# FAT42.net
KiCad netlist of a schematic drawn in Altium Designer
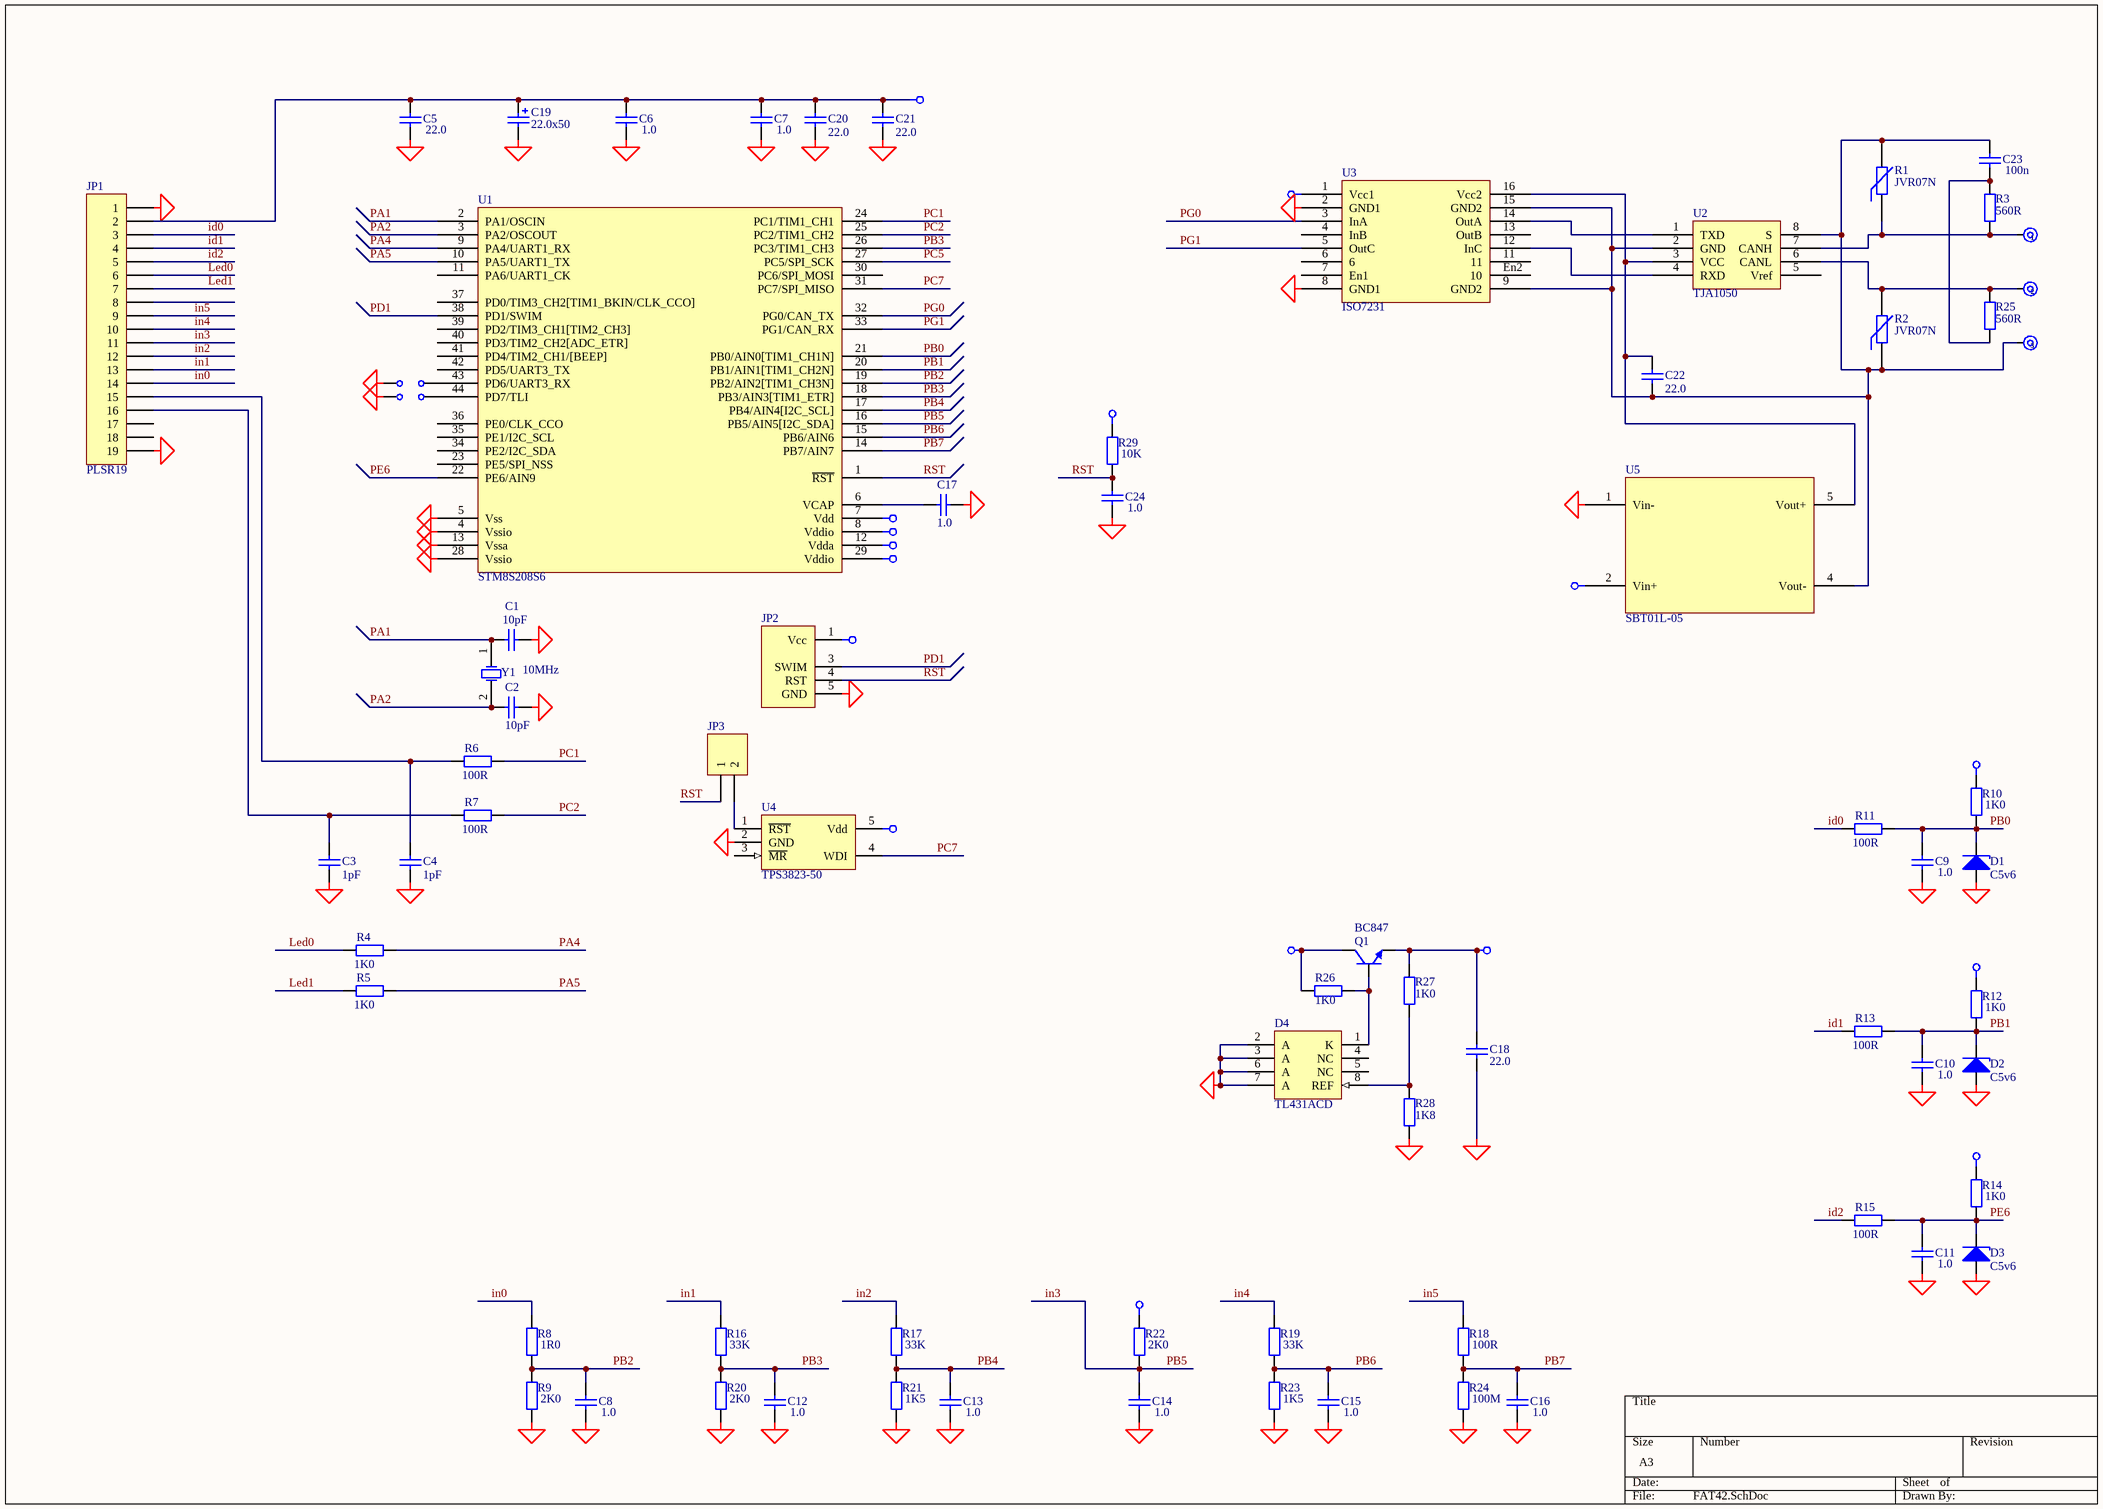
[diagram p0: FAT42.SchDoc]

(export (version "E")
  (design (tool "Eeschema 10.0.6"))
  (components
    (comp (ref "1")
      (value "~")
      (footprint "PIN2R")
      (description "Socket")
      (fields (field (name "MANUFACTURER") "Generic Components") (field (name "PUBLISHER") "Altium Limited"))
      (libsource (lib "PAL") (part "Socket_Ring"))
    )
    (comp (ref "2")
      (value "~")
      (footprint "PIN2R")
      (description "Socket")
      (fields (field (name "MANUFACTURER") "Generic Components") (field (name "PUBLISHER") "Altium Limited"))
      (libsource (lib "PAL") (part "Socket_Ring"))
    )
    (comp (ref "3")
      (value "~")
      (footprint "PIN2R")
      (description "Socket")
      (fields (field (name "MANUFACTURER") "Generic Components") (field (name "PUBLISHER") "Altium Limited"))
      (libsource (lib "PAL") (part "Socket_Ring"))
    )
    (comp (ref "C1")
      (value "10pF")
      (footprint "_1206")
      (description "Capacitor (Semiconductor SIM Model)")
      (fields (field (name "MANUFACTURER") "Generic Components") (field (name "PUBLISHER") "Altium Limited"))
      (libsource (lib "Miscellaneous Devices") (part "Cap Semi"))
    )
    (comp (ref "C2")
      (value "10pF")
      (footprint "_1206")
      (description "Capacitor (Semiconductor SIM Model)")
      (fields (field (name "MANUFACTURER") "Generic Components") (field (name "PUBLISHER") "Altium Limited"))
      (libsource (lib "Miscellaneous Devices") (part "Cap Semi"))
    )
    (comp (ref "C3")
      (value "1pF")
      (footprint "_1206")
      (description "Capacitor (Semiconductor SIM Model)")
      (fields (field (name "MANUFACTURER") "Generic Components") (field (name "PUBLISHER") "Altium Limited"))
      (libsource (lib "Miscellaneous Devices") (part "Cap Semi"))
    )
    (comp (ref "C4")
      (value "1pF")
      (footprint "_1206")
      (description "Capacitor (Semiconductor SIM Model)")
      (fields (field (name "MANUFACTURER") "Generic Components") (field (name "PUBLISHER") "Altium Limited"))
      (libsource (lib "Miscellaneous Devices") (part "Cap Semi"))
    )
    (comp (ref "C5")
      (value "22.0")
      (footprint "_1206")
      (description "Capacitor (Semiconductor SIM Model)")
      (fields (field (name "MANUFACTURER") "Generic Components") (field (name "PUBLISHER") "Altium Limited"))
      (libsource (lib "Miscellaneous Devices") (part "Cap Semi"))
    )
    (comp (ref "C6")
      (value "1.0")
      (footprint "_1206")
      (description "Capacitor (Semiconductor SIM Model)")
      (fields (field (name "MANUFACTURER") "Generic Components") (field (name "PUBLISHER") "Altium Limited"))
      (libsource (lib "Miscellaneous Devices") (part "Cap Semi"))
    )
    (comp (ref "C7")
      (value "1.0")
      (footprint "_1206")
      (description "Capacitor (Semiconductor SIM Model)")
      (fields (field (name "MANUFACTURER") "Generic Components") (field (name "PUBLISHER") "Altium Limited"))
      (libsource (lib "Miscellaneous Devices") (part "Cap Semi"))
    )
    (comp (ref "C8")
      (value "1.0")
      (footprint "_1206")
      (description "Capacitor (Semiconductor SIM Model)")
      (fields (field (name "MANUFACTURER") "Generic Components") (field (name "PUBLISHER") "Altium Limited"))
      (libsource (lib "Miscellaneous Devices") (part "Cap Semi"))
    )
    (comp (ref "C9")
      (value "1.0")
      (footprint "_1206")
      (description "Capacitor (Semiconductor SIM Model)")
      (fields (field (name "MANUFACTURER") "Generic Components") (field (name "PUBLISHER") "Altium Limited"))
      (libsource (lib "Miscellaneous Devices") (part "Cap Semi"))
    )
    (comp (ref "C10")
      (value "1.0")
      (footprint "_1206")
      (description "Capacitor (Semiconductor SIM Model)")
      (fields (field (name "MANUFACTURER") "Generic Components") (field (name "PUBLISHER") "Altium Limited"))
      (libsource (lib "Miscellaneous Devices") (part "Cap Semi"))
    )
    (comp (ref "C11")
      (value "1.0")
      (footprint "_1206")
      (description "Capacitor (Semiconductor SIM Model)")
      (fields (field (name "MANUFACTURER") "Generic Components") (field (name "PUBLISHER") "Altium Limited"))
      (libsource (lib "Miscellaneous Devices") (part "Cap Semi"))
    )
    (comp (ref "C12")
      (value "1.0")
      (footprint "_1206")
      (description "Capacitor (Semiconductor SIM Model)")
      (fields (field (name "MANUFACTURER") "Generic Components") (field (name "PUBLISHER") "Altium Limited"))
      (libsource (lib "Miscellaneous Devices") (part "Cap Semi"))
    )
    (comp (ref "C13")
      (value "1.0")
      (footprint "_1206")
      (description "Capacitor (Semiconductor SIM Model)")
      (fields (field (name "MANUFACTURER") "Generic Components") (field (name "PUBLISHER") "Altium Limited"))
      (libsource (lib "Miscellaneous Devices") (part "Cap Semi"))
    )
    (comp (ref "C14")
      (value "1.0")
      (footprint "_1206")
      (description "Capacitor (Semiconductor SIM Model)")
      (fields (field (name "MANUFACTURER") "Generic Components") (field (name "PUBLISHER") "Altium Limited"))
      (libsource (lib "Miscellaneous Devices") (part "Cap Semi"))
    )
    (comp (ref "C15")
      (value "1.0")
      (footprint "_1206")
      (description "Capacitor (Semiconductor SIM Model)")
      (fields (field (name "MANUFACTURER") "Generic Components") (field (name "PUBLISHER") "Altium Limited"))
      (libsource (lib "Miscellaneous Devices") (part "Cap Semi"))
    )
    (comp (ref "C16")
      (value "1.0")
      (footprint "_1206")
      (description "Capacitor (Semiconductor SIM Model)")
      (fields (field (name "MANUFACTURER") "Generic Components") (field (name "PUBLISHER") "Altium Limited"))
      (libsource (lib "Miscellaneous Devices") (part "Cap Semi"))
    )
    (comp (ref "C17")
      (value "1.0")
      (footprint "_1206")
      (description "Capacitor (Semiconductor SIM Model)")
      (fields (field (name "MANUFACTURER") "Generic Components") (field (name "PUBLISHER") "Altium Limited"))
      (libsource (lib "Miscellaneous Devices") (part "Cap Semi"))
    )
    (comp (ref "C18")
      (value "22.0")
      (footprint "_1206")
      (description "Capacitor (Semiconductor SIM Model)")
      (fields (field (name "MANUFACTURER") "Generic Components") (field (name "PUBLISHER") "Altium Limited"))
      (libsource (lib "Miscellaneous Devices") (part "Cap Semi"))
    )
    (comp (ref "C19")
      (value "22.0x50")
      (footprint "el3")
      (description "Polarized Capacitor (Radial)")
      (fields (field (name "MANUFACTURER") "Generic Components") (field (name "PUBLISHER") "Altium Limited"))
      (libsource (lib "PAL") (part "Cap Pol1"))
    )
    (comp (ref "C20")
      (value "22.0")
      (footprint "_1206")
      (description "Capacitor (Semiconductor SIM Model)")
      (fields (field (name "MANUFACTURER") "Generic Components") (field (name "PUBLISHER") "Altium Limited"))
      (libsource (lib "Miscellaneous Devices") (part "Cap Semi"))
    )
    (comp (ref "C21")
      (value "22.0")
      (footprint "_1206")
      (description "Capacitor (Semiconductor SIM Model)")
      (fields (field (name "MANUFACTURER") "Generic Components") (field (name "PUBLISHER") "Altium Limited"))
      (libsource (lib "Miscellaneous Devices") (part "Cap Semi"))
    )
    (comp (ref "C22")
      (value "22.0")
      (footprint "_1206")
      (description "Capacitor (Semiconductor SIM Model)")
      (fields (field (name "MANUFACTURER") "Generic Components") (field (name "PUBLISHER") "Altium Limited"))
      (libsource (lib "Miscellaneous Devices") (part "Cap Semi"))
    )
    (comp (ref "C23")
      (value "100n")
      (footprint "_1206")
      (description "Capacitor (Semiconductor SIM Model)")
      (fields (field (name "MANUFACTURER") "Generic Components") (field (name "PUBLISHER") "Altium Limited"))
      (libsource (lib "Miscellaneous Devices") (part "Cap Semi"))
    )
    (comp (ref "C24")
      (value "1.0")
      (footprint "_1206")
      (description "Capacitor (Semiconductor SIM Model)")
      (fields (field (name "MANUFACTURER") "Generic Components") (field (name "PUBLISHER") "Altium Limited"))
      (libsource (lib "Miscellaneous Devices") (part "Cap Semi"))
    )
    (comp (ref "D1")
      (value "C5v6")
      (footprint "_1206d")
      (description "Default Diode")
      (fields (field (name "MANUFACTURER") "Generic Components") (field (name "PUBLISHER") "Altium Limited"))
      (libsource (lib "PAL") (part "Zener"))
    )
    (comp (ref "D2")
      (value "C5v6")
      (footprint "_1206d")
      (description "Default Diode")
      (fields (field (name "MANUFACTURER") "Generic Components") (field (name "PUBLISHER") "Altium Limited"))
      (libsource (lib "PAL") (part "Zener"))
    )
    (comp (ref "D3")
      (value "C5v6")
      (footprint "_1206d")
      (description "Default Diode")
      (fields (field (name "MANUFACTURER") "Generic Components") (field (name "PUBLISHER") "Altium Limited"))
      (libsource (lib "PAL") (part "Zener"))
    )
    (comp (ref "D4")
      (value "TL431ACD")
      (footprint "SO-G8")
      (description "Programmable Precision Reference")
      (fields (field (name "MANUFACTURER") "Motorola") (field (name "PUBLISHER") "Altium Limited"))
      (libsource (lib "Motorola Power Management Voltage Reference") (part "TL431ACD"))
    )
    (comp (ref "J1")
      (value "~")
      (footprint "jmp")
      (description "Switch")
      (fields (field (name "MANUFACTURER") "Generic Components") (field (name "PUBLISHER") "Altium Limited"))
      (libsource (lib "PAL") (part "JMP"))
    )
    (comp (ref "J2")
      (value "~")
      (footprint "jmp")
      (description "Switch")
      (fields (field (name "MANUFACTURER") "Generic Components") (field (name "PUBLISHER") "Altium Limited"))
      (libsource (lib "PAL") (part "JMP"))
    )
    (comp (ref "JP1")
      (value "PLSR19")
      (footprint "HDR1X19")
      (description "Header, 19-Pin")
      (fields (field (name "MANUFACTURER") "Generic Components") (field (name "PUBLISHER") "Altium Limited"))
      (libsource (lib "Miscellaneous Connectors") (part "Header 19"))
    )
    (comp (ref "JP2") (value "~") (footprint "HDR1X5_uart") (libsource (lib "PAL") (part "SWIM_CONN")))
    (comp (ref "JP3")
      (value "PLS2")
      (footprint "HDR1X2")
      (description "Header, 2-Pin")
      (fields (field (name "MANUFACTURER") "Generic Components") (field (name "PUBLISHER") "Altium Limited"))
      (libsource (lib "Miscellaneous Connectors") (part "Header 2"))
    )
    (comp (ref "Q1")
      (value "BC847")
      (footprint "SO-G3")
      (description "General Purpose Transistor NPN Silicon")
      (fields (field (name "MANUFACTURER") "Motorola") (field (name "PUBLISHER") "Altium Limited"))
      (libsource (lib "PAL") (part "BC847ALT1"))
    )
    (comp (ref "R1")
      (value "JVR07N")
      (footprint "JVR07N")
      (description "Varistor (Voltage-Sensitive Resistor)")
      (fields (field (name "MANUFACTURER") "Generic Components") (field (name "PUBLISHER") "Altium Limited"))
      (libsource (lib "Miscellaneous Devices") (part "Res Varistor"))
    )
    (comp (ref "R2")
      (value "JVR07N")
      (footprint "JVR07N")
      (description "Varistor (Voltage-Sensitive Resistor)")
      (fields (field (name "MANUFACTURER") "Generic Components") (field (name "PUBLISHER") "Altium Limited"))
      (libsource (lib "Miscellaneous Devices") (part "Res Varistor"))
    )
    (comp (ref "R3")
      (value "560R")
      (footprint "_1206")
      (description "Resistor")
      (fields (field (name "MANUFACTURER") "Generic Components") (field (name "PUBLISHER") "Altium Limited"))
      (libsource (lib "") (part "Res2_1"))
    )
    (comp (ref "R4")
      (value "1K0")
      (footprint "_1206")
      (description "Resistor")
      (fields (field (name "MANUFACTURER") "Generic Components") (field (name "PUBLISHER") "Altium Limited"))
      (libsource (lib "") (part "Res2_1"))
    )
    (comp (ref "R5")
      (value "1K0")
      (footprint "_1206")
      (description "Resistor")
      (fields (field (name "MANUFACTURER") "Generic Components") (field (name "PUBLISHER") "Altium Limited"))
      (libsource (lib "") (part "Res2_1"))
    )
    (comp (ref "R6")
      (value "100R")
      (footprint "_1206")
      (description "Resistor")
      (fields (field (name "MANUFACTURER") "Generic Components") (field (name "PUBLISHER") "Altium Limited"))
      (libsource (lib "") (part "Res2_2"))
    )
    (comp (ref "R7")
      (value "100R")
      (footprint "_1206")
      (description "Resistor")
      (fields (field (name "MANUFACTURER") "Generic Components") (field (name "PUBLISHER") "Altium Limited"))
      (libsource (lib "") (part "Res2_2"))
    )
    (comp (ref "R8")
      (value "1R0")
      (footprint "_1206")
      (description "Resistor")
      (fields (field (name "MANUFACTURER") "Generic Components") (field (name "PUBLISHER") "Altium Limited"))
      (libsource (lib "Miscellaneous Devices") (part "Res2"))
    )
    (comp (ref "R9")
      (value "2K0")
      (footprint "_1206")
      (description "Resistor")
      (fields (field (name "MANUFACTURER") "Generic Components") (field (name "PUBLISHER") "Altium Limited"))
      (libsource (lib "Miscellaneous Devices") (part "Res2"))
    )
    (comp (ref "R10")
      (value "1K0")
      (footprint "_1206")
      (description "Resistor")
      (fields (field (name "MANUFACTURER") "Generic Components") (field (name "PUBLISHER") "Altium Limited"))
      (libsource (lib "") (part "Res2_4"))
    )
    (comp (ref "R11")
      (value "100R")
      (footprint "_1206")
      (description "Resistor")
      (fields (field (name "MANUFACTURER") "Generic Components") (field (name "PUBLISHER") "Altium Limited"))
      (libsource (lib "") (part "Res2_2"))
    )
    (comp (ref "R12")
      (value "1K0")
      (footprint "_1206")
      (description "Resistor")
      (fields (field (name "MANUFACTURER") "Generic Components") (field (name "PUBLISHER") "Altium Limited"))
      (libsource (lib "") (part "Res2_4"))
    )
    (comp (ref "R13")
      (value "100R")
      (footprint "_1206")
      (description "Resistor")
      (fields (field (name "MANUFACTURER") "Generic Components") (field (name "PUBLISHER") "Altium Limited"))
      (libsource (lib "") (part "Res2_2"))
    )
    (comp (ref "R14")
      (value "1K0")
      (footprint "_1206")
      (description "Resistor")
      (fields (field (name "MANUFACTURER") "Generic Components") (field (name "PUBLISHER") "Altium Limited"))
      (libsource (lib "") (part "Res2_4"))
    )
    (comp (ref "R15")
      (value "100R")
      (footprint "_1206")
      (description "Resistor")
      (fields (field (name "MANUFACTURER") "Generic Components") (field (name "PUBLISHER") "Altium Limited"))
      (libsource (lib "") (part "Res2_2"))
    )
    (comp (ref "R16")
      (value "33K")
      (footprint "_1206")
      (description "Resistor")
      (fields (field (name "MANUFACTURER") "Generic Components") (field (name "PUBLISHER") "Altium Limited"))
      (libsource (lib "Miscellaneous Devices") (part "Res2"))
    )
    (comp (ref "R17")
      (value "33K")
      (footprint "_1206")
      (description "Resistor")
      (fields (field (name "MANUFACTURER") "Generic Components") (field (name "PUBLISHER") "Altium Limited"))
      (libsource (lib "Miscellaneous Devices") (part "Res2"))
    )
    (comp (ref "R18")
      (value "100R")
      (footprint "_1206")
      (description "Resistor")
      (fields (field (name "MANUFACTURER") "Generic Components") (field (name "PUBLISHER") "Altium Limited"))
      (libsource (lib "Miscellaneous Devices") (part "Res2"))
    )
    (comp (ref "R19")
      (value "33K")
      (footprint "_1206")
      (description "Resistor")
      (fields (field (name "MANUFACTURER") "Generic Components") (field (name "PUBLISHER") "Altium Limited"))
      (libsource (lib "Miscellaneous Devices") (part "Res2"))
    )
    (comp (ref "R20")
      (value "2K0")
      (footprint "_1206")
      (description "Resistor")
      (fields (field (name "MANUFACTURER") "Generic Components") (field (name "PUBLISHER") "Altium Limited"))
      (libsource (lib "Miscellaneous Devices") (part "Res2"))
    )
    (comp (ref "R21")
      (value "1K5")
      (footprint "_1206")
      (description "Resistor")
      (fields (field (name "MANUFACTURER") "Generic Components") (field (name "PUBLISHER") "Altium Limited"))
      (libsource (lib "Miscellaneous Devices") (part "Res2"))
    )
    (comp (ref "R22")
      (value "2K0")
      (footprint "_1206")
      (description "Resistor")
      (fields (field (name "MANUFACTURER") "Generic Components") (field (name "PUBLISHER") "Altium Limited"))
      (libsource (lib "Miscellaneous Devices") (part "Res2"))
    )
    (comp (ref "R23")
      (value "1K5")
      (footprint "_1206")
      (description "Resistor")
      (fields (field (name "MANUFACTURER") "Generic Components") (field (name "PUBLISHER") "Altium Limited"))
      (libsource (lib "Miscellaneous Devices") (part "Res2"))
    )
    (comp (ref "R24")
      (value "100M")
      (footprint "_1206")
      (description "Resistor")
      (fields (field (name "MANUFACTURER") "Generic Components") (field (name "PUBLISHER") "Altium Limited"))
      (libsource (lib "Miscellaneous Devices") (part "Res2"))
    )
    (comp (ref "R25")
      (value "560R")
      (footprint "_1206")
      (description "Resistor")
      (fields (field (name "MANUFACTURER") "Generic Components") (field (name "PUBLISHER") "Altium Limited"))
      (libsource (lib "") (part "Res2_1"))
    )
    (comp (ref "R26")
      (value "1K0")
      (footprint "_1206")
      (description "Resistor")
      (fields (field (name "MANUFACTURER") "Generic Components") (field (name "PUBLISHER") "Altium Limited"))
      (libsource (lib "") (part "Res2_3"))
    )
    (comp (ref "R27")
      (value "1K0")
      (footprint "_1206")
      (description "Resistor")
      (fields (field (name "MANUFACTURER") "Generic Components") (field (name "PUBLISHER") "Altium Limited"))
      (libsource (lib "") (part "Res2_1"))
    )
    (comp (ref "R28")
      (value "1K8")
      (footprint "_1206")
      (description "Resistor")
      (fields (field (name "MANUFACTURER") "Generic Components") (field (name "PUBLISHER") "Altium Limited"))
      (libsource (lib "") (part "Res2_1"))
    )
    (comp (ref "R29")
      (value "10K")
      (footprint "_1206")
      (description "Resistor")
      (fields (field (name "MANUFACTURER") "Generic Components") (field (name "PUBLISHER") "Altium Limited"))
      (libsource (lib "") (part "Res2_4"))
    )
    (comp (ref "U1")
      (value "STM8S208S6")
      (footprint "QFP10X10-G44/G10N")
      (libsource (lib "PAL") (part "STM8S208S6"))
    )
    (comp (ref "U2") (value "TJA1050") (footprint "SO-G8/D5") (libsource (lib "PAL") (part "TJA1050")))
    (comp (ref "U3") (value "ISO7231") (footprint "SO-G16/D10.4") (libsource (lib "PAL") (part "ISO7231")))
    (comp (ref "U4")
      (value "TPS3823-50")
      (footprint "SO-G5/P.95")
      (description "Reset IC")
      (fields
        (field (name "MANUFACTURER") "National Semiconductor")
        (field (name "PUBLISHER") "Altium Limited")
      )
      (libsource (lib "PAL") (part "TPS3823"))
    )
    (comp (ref "U5") (value "SBT01L-05") (footprint "SBT01DET01") (libsource (lib "PAL") (part "SBT01L")))
    (comp (ref "Y1")
      (value "10MHz")
      (footprint "QWARZ1")
      (description "Crystal Oscillator")
      (fields (field (name "MANUFACTURER") "Generic Components") (field (name "PUBLISHER") "Altium Limited"))
      (libsource (lib "Miscellaneous Devices") (part "XTAL"))
    )
  )
  (nets
    (net (code "1") (name "+5v") (class "Default")
      (node (ref "C19") (pin "1") (pinfunction "1_1") (pintype "passive"))
      (node (ref "C20") (pin "1") (pinfunction "1_1") (pintype "passive"))
      (node (ref "C21") (pin "1") (pinfunction "1_1") (pintype "passive"))
      (node (ref "C5") (pin "2") (pinfunction "2_2") (pintype "passive"))
      (node (ref "C6") (pin "2") (pinfunction "2_2") (pintype "passive"))
      (node (ref "C7") (pin "2") (pinfunction "2_2") (pintype "passive"))
      (node (ref "JP1") (pin "2") (pinfunction "2_2") (pintype "passive"))
      (node (ref "JP2") (pin "1") (pinfunction "Vcc_1") (pintype "passive"))
      (node (ref "Q1") (pin "3") (pinfunction "C_3") (pintype "passive"))
      (node (ref "R10") (pin "1") (pinfunction "1_1") (pintype "passive"))
      (node (ref "R12") (pin "1") (pinfunction "1_1") (pintype "passive"))
      (node (ref "R14") (pin "1") (pinfunction "1_1") (pintype "passive"))
      (node (ref "R22") (pin "2") (pinfunction "2_2") (pintype "passive"))
      (node (ref "R26") (pin "1") (pinfunction "1_1") (pintype "passive"))
      (node (ref "R29") (pin "1") (pinfunction "1_1") (pintype "passive"))
      (node (ref "U1") (pin "29") (pinfunction "Vddio_29") (pintype "passive"))
      (node (ref "U1") (pin "7") (pinfunction "Vdd_7") (pintype "passive"))
      (node (ref "U1") (pin "8") (pinfunction "Vddio_8") (pintype "passive"))
      (node (ref "U3") (pin "1") (pinfunction "Vcc1_1") (pintype "passive"))
      (node (ref "U4") (pin "5") (pinfunction "Vdd_5") (pintype "power_in"))
      (node (ref "U5") (pin "2") (pinfunction "Vin+_2") (pintype "passive"))
    )
    (net (code "2") (name "/Led0") (class "Default")
      (node (ref "JP1") (pin "6") (pinfunction "6_6") (pintype "passive"))
      (node (ref "R4") (pin "1") (pinfunction "1_1") (pintype "passive"))
    )
    (net (code "3") (name "/Led1") (class "Default")
      (node (ref "JP1") (pin "7") (pinfunction "7_7") (pintype "passive"))
      (node (ref "R5") (pin "1") (pinfunction "1_1") (pintype "passive"))
    )
    (net (code "4") (name "/PA1") (class "Default")
      (node (ref "C1") (pin "2") (pinfunction "2_2") (pintype "passive"))
      (node (ref "U1") (pin "2") (pinfunction "PA1/OSCIN_2") (pintype "passive"))
      (node (ref "Y1") (pin "1") (pinfunction "OSC1_1") (pintype "passive"))
    )
    (net (code "5") (name "/PA2") (class "Default")
      (node (ref "C2") (pin "2") (pinfunction "2_2") (pintype "passive"))
      (node (ref "U1") (pin "3") (pinfunction "PA2/OSCOUT_3") (pintype "passive"))
      (node (ref "Y1") (pin "2") (pinfunction "OSC2_2") (pintype "passive"))
    )
    (net (code "6") (name "/PA4") (class "Default")
      (node (ref "R4") (pin "2") (pinfunction "2_2") (pintype "passive"))
      (node (ref "U1") (pin "9") (pinfunction "PA4/UART1_RX_9") (pintype "passive"))
    )
    (net (code "7") (name "/PA5") (class "Default")
      (node (ref "R5") (pin "2") (pinfunction "2_2") (pintype "passive"))
      (node (ref "U1") (pin "10") (pinfunction "PA5/UART1_TX_10") (pintype "passive"))
    )
    (net (code "8") (name "/PB0") (class "Default")
      (node (ref "C9") (pin "2") (pinfunction "2_2") (pintype "passive"))
      (node (ref "D1") (pin "2") (pinfunction "K_2") (pintype "passive"))
      (node (ref "R10") (pin "2") (pinfunction "2_2") (pintype "passive"))
      (node (ref "R11") (pin "1") (pinfunction "1_1") (pintype "passive"))
      (node (ref "U1") (pin "21") (pinfunction "PB0/AIN0[TIM1_CH1N]_21") (pintype "passive"))
    )
    (net (code "9") (name "/PB1") (class "Default")
      (node (ref "C10") (pin "2") (pinfunction "2_2") (pintype "passive"))
      (node (ref "D2") (pin "2") (pinfunction "K_2") (pintype "passive"))
      (node (ref "R12") (pin "2") (pinfunction "2_2") (pintype "passive"))
      (node (ref "R13") (pin "1") (pinfunction "1_1") (pintype "passive"))
      (node (ref "U1") (pin "20") (pinfunction "PB1/AIN1[TIM1_CH2N]_20") (pintype "passive"))
    )
    (net (code "10") (name "/PB2") (class "Default")
      (node (ref "C8") (pin "2") (pinfunction "2_2") (pintype "passive"))
      (node (ref "R8") (pin "1") (pinfunction "1_1") (pintype "passive"))
      (node (ref "R9") (pin "2") (pinfunction "2_2") (pintype "passive"))
      (node (ref "U1") (pin "19") (pinfunction "PB2/AIN2[TIM1_CH3N]_19") (pintype "passive"))
    )
    (net (code "11") (name "/PB3") (class "Default")
      (node (ref "C12") (pin "2") (pinfunction "2_2") (pintype "passive"))
      (node (ref "R16") (pin "1") (pinfunction "1_1") (pintype "passive"))
      (node (ref "R20") (pin "2") (pinfunction "2_2") (pintype "passive"))
      (node (ref "U1") (pin "18") (pinfunction "PB3/AIN3[TIM1_ETR]_18") (pintype "passive"))
      (node (ref "U1") (pin "26") (pinfunction "PC3/TIM1_CH3_26") (pintype "passive"))
    )
    (net (code "12") (name "/PB4") (class "Default")
      (node (ref "C13") (pin "2") (pinfunction "2_2") (pintype "passive"))
      (node (ref "R17") (pin "1") (pinfunction "1_1") (pintype "passive"))
      (node (ref "R21") (pin "2") (pinfunction "2_2") (pintype "passive"))
      (node (ref "U1") (pin "17") (pinfunction "PB4/AIN4[I2C_SCL]_17") (pintype "passive"))
    )
    (net (code "13") (name "/PB5") (class "Default")
      (node (ref "C14") (pin "2") (pinfunction "2_2") (pintype "passive"))
      (node (ref "JP1") (pin "11") (pinfunction "11_11") (pintype "passive"))
      (node (ref "R22") (pin "1") (pinfunction "1_1") (pintype "passive"))
      (node (ref "U1") (pin "16") (pinfunction "PB5/AIN5[I2C_SDA]_16") (pintype "passive"))
    )
    (net (code "14") (name "/PB6") (class "Default")
      (node (ref "C15") (pin "2") (pinfunction "2_2") (pintype "passive"))
      (node (ref "R19") (pin "1") (pinfunction "1_1") (pintype "passive"))
      (node (ref "R23") (pin "2") (pinfunction "2_2") (pintype "passive"))
      (node (ref "U1") (pin "15") (pinfunction "PB6/AIN6_15") (pintype "passive"))
    )
    (net (code "15") (name "/PB7") (class "Default")
      (node (ref "C16") (pin "2") (pinfunction "2_2") (pintype "passive"))
      (node (ref "R18") (pin "1") (pinfunction "1_1") (pintype "passive"))
      (node (ref "R24") (pin "2") (pinfunction "2_2") (pintype "passive"))
      (node (ref "U1") (pin "14") (pinfunction "PB7/AIN7_14") (pintype "passive"))
    )
    (net (code "16") (name "/PC1") (class "Default")
      (node (ref "R6") (pin "1") (pinfunction "1_1") (pintype "passive"))
      (node (ref "U1") (pin "24") (pinfunction "PC1/TIM1_CH1_24") (pintype "passive"))
    )
    (net (code "17") (name "/PC2") (class "Default")
      (node (ref "R7") (pin "1") (pinfunction "1_1") (pintype "passive"))
      (node (ref "U1") (pin "25") (pinfunction "PC2/TIM1_CH2_25") (pintype "passive"))
    )
    (net (code "18") (name "/PC5") (class "Default")
      (node (ref "U1") (pin "27") (pinfunction "PC5/SPI_SCK_27") (pintype "passive"))
    )
    (net (code "19") (name "/PC7") (class "Default")
      (node (ref "U1") (pin "31") (pinfunction "PC7/SPI_MISO_31") (pintype "passive"))
      (node (ref "U4") (pin "4") (pinfunction "WDI_4") (pintype "passive"))
    )
    (net (code "20") (name "/PD1") (class "Default")
      (node (ref "JP2") (pin "3") (pinfunction "SWIM_3") (pintype "passive"))
      (node (ref "U1") (pin "38") (pinfunction "PD1/SWIM_38") (pintype "passive"))
    )
    (net (code "21") (name "/PE6") (class "Default")
      (node (ref "C11") (pin "2") (pinfunction "2_2") (pintype "passive"))
      (node (ref "D3") (pin "2") (pinfunction "K_2") (pintype "passive"))
      (node (ref "R14") (pin "2") (pinfunction "2_2") (pintype "passive"))
      (node (ref "R15") (pin "1") (pinfunction "1_1") (pintype "passive"))
      (node (ref "U1") (pin "22") (pinfunction "PE6/AIN9_22") (pintype "passive"))
    )
    (net (code "22") (name "/PG0") (class "Default")
      (node (ref "U1") (pin "32") (pinfunction "PG0/CAN_TX_32") (pintype "passive"))
      (node (ref "U3") (pin "3") (pinfunction "InA_3") (pintype "passive"))
    )
    (net (code "23") (name "/PG1") (class "Default")
      (node (ref "U1") (pin "33") (pinfunction "PG1/CAN_RX_33") (pintype "passive"))
      (node (ref "U3") (pin "5") (pinfunction "OutC_5") (pintype "passive"))
    )
    (net (code "24") (name "/RST") (class "Default")
      (node (ref "C24") (pin "2") (pinfunction "2_2") (pintype "passive"))
      (node (ref "JP2") (pin "4") (pinfunction "RST_4") (pintype "passive"))
      (node (ref "JP3") (pin "1") (pinfunction "1_1") (pintype "passive"))
      (node (ref "R29") (pin "2") (pinfunction "2_2") (pintype "passive"))
      (node (ref "U1") (pin "1") (pinfunction "~{RST}_1") (pintype "passive"))
    )
    (net (code "25") (name "/id0") (class "Default")
      (node (ref "JP1") (pin "3") (pinfunction "3_3") (pintype "passive"))
      (node (ref "R11") (pin "2") (pinfunction "2_2") (pintype "passive"))
    )
    (net (code "26") (name "/id1") (class "Default")
      (node (ref "JP1") (pin "4") (pinfunction "4_4") (pintype "passive"))
      (node (ref "R13") (pin "2") (pinfunction "2_2") (pintype "passive"))
    )
    (net (code "27") (name "/id2") (class "Default")
      (node (ref "JP1") (pin "5") (pinfunction "5_5") (pintype "passive"))
      (node (ref "R15") (pin "2") (pinfunction "2_2") (pintype "passive"))
    )
    (net (code "28") (name "/in0") (class "Default")
      (node (ref "JP1") (pin "14") (pinfunction "14_14") (pintype "passive"))
      (node (ref "R8") (pin "2") (pinfunction "2_2") (pintype "passive"))
    )
    (net (code "29") (name "/in1") (class "Default")
      (node (ref "JP1") (pin "13") (pinfunction "13_13") (pintype "passive"))
      (node (ref "R16") (pin "2") (pinfunction "2_2") (pintype "passive"))
    )
    (net (code "30") (name "/in2") (class "Default")
      (node (ref "JP1") (pin "12") (pinfunction "12_12") (pintype "passive"))
      (node (ref "R17") (pin "2") (pinfunction "2_2") (pintype "passive"))
    )
    (net (code "31") (name "/in4") (class "Default")
      (node (ref "JP1") (pin "10") (pinfunction "10_10") (pintype "passive"))
      (node (ref "R19") (pin "2") (pinfunction "2_2") (pintype "passive"))
    )
    (net (code "32") (name "/in5") (class "Default")
      (node (ref "JP1") (pin "9") (pinfunction "9_9") (pintype "passive"))
      (node (ref "R18") (pin "2") (pinfunction "2_2") (pintype "passive"))
    )
    (net (code "33") (name "GND") (class "Default")
      (node (ref "C1") (pin "1") (pinfunction "1_1") (pintype "passive"))
      (node (ref "C10") (pin "1") (pinfunction "1_1") (pintype "passive"))
      (node (ref "C11") (pin "1") (pinfunction "1_1") (pintype "passive"))
      (node (ref "C12") (pin "1") (pinfunction "1_1") (pintype "passive"))
      (node (ref "C13") (pin "1") (pinfunction "1_1") (pintype "passive"))
      (node (ref "C14") (pin "1") (pinfunction "1_1") (pintype "passive"))
      (node (ref "C15") (pin "1") (pinfunction "1_1") (pintype "passive"))
      (node (ref "C16") (pin "1") (pinfunction "1_1") (pintype "passive"))
      (node (ref "C17") (pin "1") (pinfunction "1_1") (pintype "passive"))
      (node (ref "C18") (pin "1") (pinfunction "1_1") (pintype "passive"))
      (node (ref "C19") (pin "2") (pinfunction "2_2") (pintype "passive"))
      (node (ref "C2") (pin "1") (pinfunction "1_1") (pintype "passive"))
      (node (ref "C20") (pin "2") (pinfunction "2_2") (pintype "passive"))
      (node (ref "C21") (pin "2") (pinfunction "2_2") (pintype "passive"))
      (node (ref "C24") (pin "1") (pinfunction "1_1") (pintype "passive"))
      (node (ref "C3") (pin "1") (pinfunction "1_1") (pintype "passive"))
      (node (ref "C4") (pin "1") (pinfunction "1_1") (pintype "passive"))
      (node (ref "C5") (pin "1") (pinfunction "1_1") (pintype "passive"))
      (node (ref "C6") (pin "1") (pinfunction "1_1") (pintype "passive"))
      (node (ref "C7") (pin "1") (pinfunction "1_1") (pintype "passive"))
      (node (ref "C8") (pin "1") (pinfunction "1_1") (pintype "passive"))
      (node (ref "C9") (pin "1") (pinfunction "1_1") (pintype "passive"))
      (node (ref "D1") (pin "1") (pinfunction "A_1") (pintype "passive"))
      (node (ref "D2") (pin "1") (pinfunction "A_1") (pintype "passive"))
      (node (ref "D3") (pin "1") (pinfunction "A_1") (pintype "passive"))
      (node (ref "D4") (pin "2") (pinfunction "A_2") (pintype "passive"))
      (node (ref "D4") (pin "3") (pinfunction "A_3") (pintype "passive"))
      (node (ref "D4") (pin "6") (pinfunction "A_6") (pintype "passive"))
      (node (ref "D4") (pin "7") (pinfunction "A_7") (pintype "passive"))
      (node (ref "J1") (pin "1") (pinfunction "1_1") (pintype "passive"))
      (node (ref "J2") (pin "1") (pinfunction "1_1") (pintype "passive"))
      (node (ref "JP1") (pin "1") (pinfunction "1_1") (pintype "passive"))
      (node (ref "JP1") (pin "19") (pinfunction "19_19") (pintype "passive"))
      (node (ref "JP2") (pin "5") (pinfunction "GND_5") (pintype "passive"))
      (node (ref "R20") (pin "1") (pinfunction "1_1") (pintype "passive"))
      (node (ref "R21") (pin "1") (pinfunction "1_1") (pintype "passive"))
      (node (ref "R23") (pin "1") (pinfunction "1_1") (pintype "passive"))
      (node (ref "R24") (pin "1") (pinfunction "1_1") (pintype "passive"))
      (node (ref "R28") (pin "1") (pinfunction "1_1") (pintype "passive"))
      (node (ref "R9") (pin "1") (pinfunction "1_1") (pintype "passive"))
      (node (ref "U1") (pin "13") (pinfunction "Vssa_13") (pintype "passive"))
      (node (ref "U1") (pin "28") (pinfunction "Vssio_28") (pintype "passive"))
      (node (ref "U1") (pin "4") (pinfunction "Vssio_4") (pintype "passive"))
      (node (ref "U1") (pin "5") (pinfunction "Vss_5") (pintype "passive"))
      (node (ref "U3") (pin "2") (pinfunction "GND1_2") (pintype "passive"))
      (node (ref "U3") (pin "8") (pinfunction "GND1_8") (pintype "passive"))
      (node (ref "U4") (pin "2") (pinfunction "GND_2") (pintype "power_in"))
      (node (ref "U5") (pin "1") (pinfunction "Vin-_1") (pintype "passive"))
    )
    (net (code "34") (name "Net-(C3-Pad2)") (class "Default")
      (node (ref "C3") (pin "2") (pinfunction "2_2") (pintype "passive"))
      (node (ref "JP1") (pin "16") (pinfunction "16_16") (pintype "passive"))
      (node (ref "R7") (pin "2") (pinfunction "2_2") (pintype "passive"))
    )
    (net (code "35") (name "Net-(C4-Pad2)") (class "Default")
      (node (ref "C4") (pin "2") (pinfunction "2_2") (pintype "passive"))
      (node (ref "JP1") (pin "15") (pinfunction "15_15") (pintype "passive"))
      (node (ref "R6") (pin "2") (pinfunction "2_2") (pintype "passive"))
    )
    (net (code "36") (name "Net-(C23-Pad1)") (class "Default")
      (node (ref "C23") (pin "1") (pinfunction "1_1") (pintype "passive"))
      (node (ref "R25") (pin "1") (pinfunction "1_1") (pintype "passive"))
      (node (ref "R3") (pin "2") (pinfunction "2_2") (pintype "passive"))
    )
    (net (code "37") (name "Net-(D4-K)") (class "Default")
      (node (ref "D4") (pin "1") (pinfunction "K_1") (pintype "passive"))
      (node (ref "Q1") (pin "1") (pinfunction "B_1") (pintype "passive"))
      (node (ref "R26") (pin "2") (pinfunction "2_2") (pintype "passive"))
    )
    (net (code "38") (name "Net-(D4-REF)") (class "Default")
      (node (ref "D4") (pin "8") (pinfunction "REF_8") (pintype "input"))
      (node (ref "R27") (pin "1") (pinfunction "1_1") (pintype "passive"))
      (node (ref "R28") (pin "2") (pinfunction "2_2") (pintype "passive"))
    )
    (net (code "39") (name "Net-(U1-PD6{slash}UART3_RX)") (class "Default")
      (node (ref "J1") (pin "2") (pinfunction "2_2") (pintype "passive"))
      (node (ref "U1") (pin "43") (pinfunction "PD6/UART3_RX_43") (pintype "passive"))
    )
    (net (code "40") (name "Net-(U1-PD7{slash}TLI)") (class "Default")
      (node (ref "J2") (pin "2") (pinfunction "2_2") (pintype "passive"))
      (node (ref "U1") (pin "44") (pinfunction "PD7/TLI_44") (pintype "passive"))
    )
    (net (code "41") (name "Net-(U1-VCAP)") (class "Default")
      (node (ref "C17") (pin "2") (pinfunction "2_2") (pintype "passive"))
      (node (ref "U1") (pin "6") (pinfunction "VCAP_6") (pintype "passive"))
    )
    (net (code "42") (name "Net-(U2-CANH)") (class "Default")
      (node (ref "1") (pin "1") (pinfunction "1_1") (pintype "passive"))
      (node (ref "R1") (pin "1") (pinfunction "1_1") (pintype "passive"))
      (node (ref "R3") (pin "1") (pinfunction "1_1") (pintype "passive"))
      (node (ref "U2") (pin "7") (pinfunction "CANH_7") (pintype "passive"))
    )
    (net (code "43") (name "Net-(U2-CANL)") (class "Default")
      (node (ref "2") (pin "1") (pinfunction "1_1") (pintype "passive"))
      (node (ref "R2") (pin "2") (pinfunction "2_2") (pintype "passive"))
      (node (ref "R25") (pin "2") (pinfunction "2_2") (pintype "passive"))
      (node (ref "U2") (pin "6") (pinfunction "CANL_6") (pintype "passive"))
    )
    (net (code "44") (name "Net-(U2-GND)") (class "Default")
      (node (ref "3") (pin "1") (pinfunction "1_1") (pintype "passive"))
      (node (ref "C22") (pin "2") (pinfunction "2_2") (pintype "passive"))
      (node (ref "C23") (pin "2") (pinfunction "2_2") (pintype "passive"))
      (node (ref "R1") (pin "2") (pinfunction "2_2") (pintype "passive"))
      (node (ref "R2") (pin "1") (pinfunction "1_1") (pintype "passive"))
      (node (ref "U2") (pin "2") (pinfunction "GND_2") (pintype "passive"))
      (node (ref "U2") (pin "8") (pinfunction "S_8") (pintype "passive"))
      (node (ref "U3") (pin "15") (pinfunction "GND2_15") (pintype "passive"))
      (node (ref "U3") (pin "9") (pinfunction "GND2_9") (pintype "passive"))
      (node (ref "U5") (pin "4") (pinfunction "Vout-_4") (pintype "passive"))
    )
    (net (code "45") (name "Net-(U2-RXD)") (class "Default")
      (node (ref "U2") (pin "4") (pinfunction "RXD_4") (pintype "passive"))
      (node (ref "U3") (pin "12") (pinfunction "InC_12") (pintype "passive"))
    )
    (net (code "46") (name "Net-(U2-TXD)") (class "Default")
      (node (ref "U2") (pin "1") (pinfunction "TXD_1") (pintype "passive"))
      (node (ref "U3") (pin "14") (pinfunction "OutA_14") (pintype "passive"))
    )
    (net (code "47") (name "Net-(U2-VCC)") (class "Default")
      (node (ref "C22") (pin "1") (pinfunction "1_1") (pintype "passive"))
      (node (ref "U2") (pin "3") (pinfunction "VCC_3") (pintype "passive"))
      (node (ref "U3") (pin "16") (pinfunction "Vcc2_16") (pintype "passive"))
      (node (ref "U5") (pin "5") (pinfunction "Vout+_5") (pintype "passive"))
    )
    (net (code "48") (name "Net-(U4-~{RST})") (class "Default")
      (node (ref "JP3") (pin "2") (pinfunction "2_2") (pintype "passive"))
      (node (ref "U4") (pin "1") (pinfunction "~{RST}_1") (pintype "power_in"))
    )
    (net (code "49") (name "Uref") (class "Default")
      (node (ref "C18") (pin "2") (pinfunction "2_2") (pintype "passive"))
      (node (ref "Q1") (pin "2") (pinfunction "E_2") (pintype "passive"))
      (node (ref "R27") (pin "2") (pinfunction "2_2") (pintype "passive"))
      (node (ref "U1") (pin "12") (pinfunction "Vdda_12") (pintype "passive"))
    )
    (net (code "50") (name "unconnected-(D4-NC-Pad4)") (class "Default")
      (node (ref "D4") (pin "4") (pinfunction "NC_4") (pintype "passive"))
    )
    (net (code "51") (name "unconnected-(D4-NC-Pad5)") (class "Default")
      (node (ref "D4") (pin "5") (pinfunction "NC_5") (pintype "passive"))
    )
    (net (code "52") (name "unconnected-(JP1-Pad8)") (class "Default")
      (node (ref "JP1") (pin "8") (pinfunction "8_8") (pintype "passive"))
    )
    (net (code "53") (name "unconnected-(JP1-Pad17)") (class "Default")
      (node (ref "JP1") (pin "17") (pinfunction "17_17") (pintype "passive"))
    )
    (net (code "54") (name "unconnected-(JP1-Pad18)") (class "Default")
      (node (ref "JP1") (pin "18") (pinfunction "18_18") (pintype "passive"))
    )
    (net (code "55") (name "unconnected-(U1-PA6{slash}UART1_CK-Pad11)") (class "Default")
      (node (ref "U1") (pin "11") (pinfunction "PA6/UART1_CK_11") (pintype "passive"))
    )
    (net (code "56") (name "unconnected-(U1-PC6{slash}SPI_MOSI-Pad30)") (class "Default")
      (node (ref "U1") (pin "30") (pinfunction "PC6/SPI_MOSI_30") (pintype "passive"))
    )
    (net (code "57") (name "unconnected-(U1-PD0{slash}TIM3_CH2[TIM1_BKIN{slash}CLK_CCO]-Pad37)") (class "Default")
      (node (ref "U1") (pin "37") (pinfunction "PD0/TIM3_CH2[TIM1_BKIN/CLK_CCO]_37") (pintype "passive"))
    )
    (net (code "58") (name "unconnected-(U1-PD2{slash}TIM3_CH1[TIM2_CH3]-Pad39)") (class "Default")
      (node (ref "U1") (pin "39") (pinfunction "PD2/TIM3_CH1[TIM2_CH3]_39") (pintype "passive"))
    )
    (net (code "59") (name "unconnected-(U1-PD3{slash}TIM2_CH2[ADC_ETR]-Pad40)") (class "Default")
      (node (ref "U1") (pin "40") (pinfunction "PD3/TIM2_CH2[ADC_ETR]_40") (pintype "passive"))
    )
    (net (code "60") (name "unconnected-(U1-PD4{slash}TIM2_CH1{slash}[BEEP]-Pad41)") (class "Default")
      (node (ref "U1") (pin "41") (pinfunction "PD4/TIM2_CH1/[BEEP]_41") (pintype "passive"))
    )
    (net (code "61") (name "unconnected-(U1-PD5{slash}UART3_TX-Pad42)") (class "Default")
      (node (ref "U1") (pin "42") (pinfunction "PD5/UART3_TX_42") (pintype "passive"))
    )
    (net (code "62") (name "unconnected-(U1-PE0{slash}CLK_CCO-Pad36)") (class "Default")
      (node (ref "U1") (pin "36") (pinfunction "PE0/CLK_CCO_36") (pintype "passive"))
    )
    (net (code "63") (name "unconnected-(U1-PE1{slash}I2C_SCL-Pad35)") (class "Default")
      (node (ref "U1") (pin "35") (pinfunction "PE1/I2C_SCL_35") (pintype "passive"))
    )
    (net (code "64") (name "unconnected-(U1-PE2{slash}I2C_SDA-Pad34)") (class "Default")
      (node (ref "U1") (pin "34") (pinfunction "PE2/I2C_SDA_34") (pintype "passive"))
    )
    (net (code "65") (name "unconnected-(U1-PE5{slash}SPI_NSS-Pad23)") (class "Default")
      (node (ref "U1") (pin "23") (pinfunction "PE5/SPI_NSS_23") (pintype "passive"))
    )
    (net (code "66") (name "unconnected-(U2-Vref-Pad5)") (class "Default")
      (node (ref "U2") (pin "5") (pinfunction "Vref_5") (pintype "passive"))
    )
    (net (code "67") (name "unconnected-(U3-10-PadEn2)") (class "Default")
      (node (ref "U3") (pin "En2") (pinfunction "10_En2") (pintype "passive"))
    )
    (net (code "68") (name "unconnected-(U3-En1-Pad7)") (class "Default")
      (node (ref "U3") (pin "7") (pinfunction "En1_7") (pintype "passive"))
    )
    (net (code "69") (name "unconnected-(U3-InB-Pad4)") (class "Default")
      (node (ref "U3") (pin "4") (pinfunction "InB_4") (pintype "passive"))
    )
    (net (code "70") (name "unconnected-(U3-OutB-Pad13)") (class "Default")
      (node (ref "U3") (pin "13") (pinfunction "OutB_13") (pintype "passive"))
    )
    (net (code "71") (name "unconnected-(U3-Pad6)") (class "Default")
      (node (ref "U3") (pin "6") (pinfunction "6_6") (pintype "passive"))
    )
    (net (code "72") (name "unconnected-(U3-Pad11)") (class "Default")
      (node (ref "U3") (pin "11") (pinfunction "11_11") (pintype "passive"))
    )
    (net (code "73") (name "unconnected-(U4-~{MR}-Pad3)") (class "Default")
      (node (ref "U4") (pin "3") (pinfunction "~{MR}_3") (pintype "input"))
    )
  )
)
